# 2_10decoder1-2.net
KiCad netlist of a schematic drawn in EAGLE
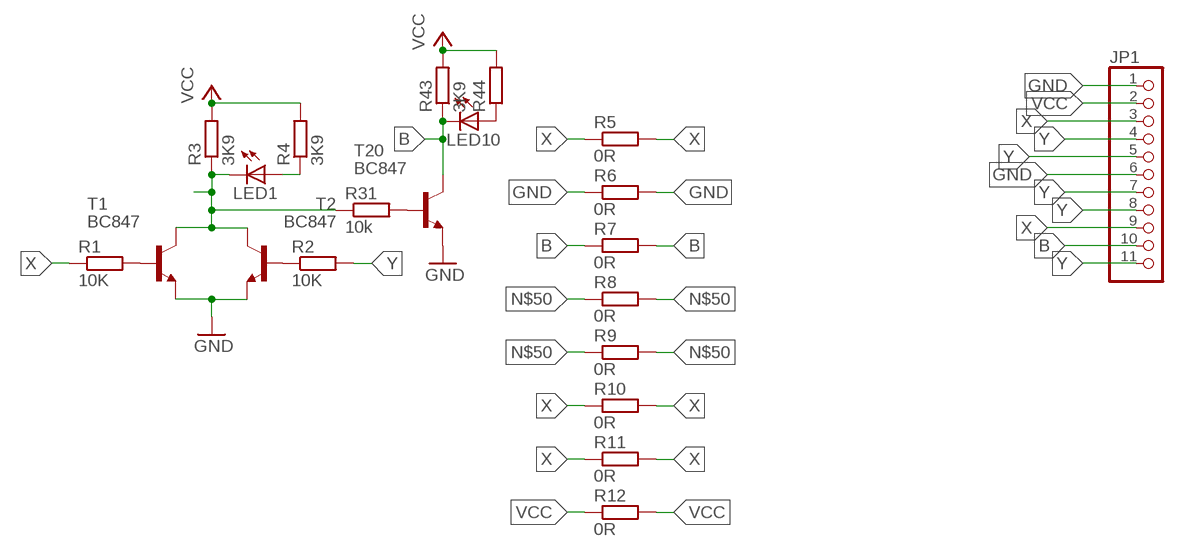
[diagram p0: schematic, sheet 1]

(export (version "E")
  (design (tool "Eeschema 10.0.6"))
  (components
    (comp (ref "JP1")
      (value "PINHD-1X11_2.54-SMD-90°")
      (footprint "eagle-import:1X11SMD_90")
      (libsource (lib "eagle-import") (part "PINHD-1X11_2.54-SMD-90°"))
    )
    (comp (ref "LED1")
      (value "LEDCHIP-LED0805")
      (footprint "eagle-import:CHIP-LED0805")
      (libsource (lib "eagle-import") (part "LEDCHIP-LED0805"))
    )
    (comp (ref "LED10")
      (value "LEDCHIP-LED0805")
      (footprint "eagle-import:CHIP-LED0805")
      (libsource (lib "eagle-import") (part "LEDCHIP-LED0805"))
    )
    (comp (ref "R1")
      (value "10K")
      (footprint "eagle-import:M0805")
      (libsource (lib "eagle-import") (part "resistor_348_R-EU_M0805"))
    )
    (comp (ref "R2")
      (value "10K")
      (footprint "eagle-import:M0805")
      (libsource (lib "eagle-import") (part "resistor_348_R-EU_M0805"))
    )
    (comp (ref "R3")
      (value "3K9")
      (footprint "eagle-import:M0805")
      (libsource (lib "eagle-import") (part "resistor_348_R-EU_M0805"))
    )
    (comp (ref "R4")
      (value "3K9")
      (footprint "eagle-import:M0805")
      (libsource (lib "eagle-import") (part "resistor_348_R-EU_M0805"))
    )
    (comp (ref "R5")
      (value "0R")
      (footprint "eagle-import:M1206")
      (libsource (lib "eagle-import") (part "R-EU_M1206"))
    )
    (comp (ref "R6")
      (value "0R")
      (footprint "eagle-import:M1206")
      (libsource (lib "eagle-import") (part "R-EU_M1206"))
    )
    (comp (ref "R7")
      (value "0R")
      (footprint "eagle-import:M1206")
      (libsource (lib "eagle-import") (part "R-EU_M1206"))
    )
    (comp (ref "R8")
      (value "0R")
      (footprint "eagle-import:M1206")
      (libsource (lib "eagle-import") (part "R-EU_M1206"))
    )
    (comp (ref "R9")
      (value "0R")
      (footprint "eagle-import:M1206")
      (libsource (lib "eagle-import") (part "R-EU_M1206"))
    )
    (comp (ref "R10")
      (value "0R")
      (footprint "eagle-import:M1206")
      (libsource (lib "eagle-import") (part "R-EU_M1206"))
    )
    (comp (ref "R11")
      (value "0R")
      (footprint "eagle-import:M1206")
      (libsource (lib "eagle-import") (part "R-EU_M1206"))
    )
    (comp (ref "R12")
      (value "0R")
      (footprint "eagle-import:M1206")
      (libsource (lib "eagle-import") (part "R-EU_M1206"))
    )
    (comp (ref "R31")
      (value "10k")
      (footprint "eagle-import:M0805")
      (libsource (lib "eagle-import") (part "resistor_348_R-EU_M0805"))
    )
    (comp (ref "R43")
      (value "3K9")
      (footprint "eagle-import:M0805")
      (libsource (lib "eagle-import") (part "resistor_348_R-EU_M0805"))
    )
    (comp (ref "R44")
      (value "R-EU_M0805")
      (footprint "eagle-import:M0805")
      (libsource (lib "eagle-import") (part "resistor_348_R-EU_M0805"))
    )
    (comp (ref "T1")
      (value "BC847")
      (footprint "eagle-import:SOT23")
      (libsource (lib "eagle-import") (part "BC847"))
    )
    (comp (ref "T2")
      (value "BC847")
      (footprint "eagle-import:SOT23")
      (libsource (lib "eagle-import") (part "BC847"))
    )
    (comp (ref "T20")
      (value "BC847")
      (footprint "eagle-import:SOT23")
      (libsource (lib "eagle-import") (part "BC847"))
    )
  )
  (nets
    (net (code "1") (name "B") (class "Default")
      (node (ref "JP1") (pin "10") (pinfunction "10_10") (pintype "passive"))
      (node (ref "LED10") (pin "C") (pinfunction "C_C") (pintype "passive"))
      (node (ref "R43") (pin "1") (pinfunction "1_1") (pintype "passive"))
      (node (ref "R7") (pin "1") (pinfunction "1_1") (pintype "passive"))
      (node (ref "R7") (pin "2") (pinfunction "2_2") (pintype "passive"))
      (node (ref "T20") (pin "3") (pinfunction "C_3") (pintype "passive"))
    )
    (net (code "2") (name "GND") (class "Default")
      (node (ref "JP1") (pin "1") (pinfunction "1_1") (pintype "passive"))
      (node (ref "JP1") (pin "6") (pinfunction "6_6") (pintype "passive"))
      (node (ref "R6") (pin "1") (pinfunction "1_1") (pintype "passive"))
      (node (ref "R6") (pin "2") (pinfunction "2_2") (pintype "passive"))
      (node (ref "T1") (pin "2") (pinfunction "E_2") (pintype "passive"))
      (node (ref "T2") (pin "2") (pinfunction "E_2") (pintype "passive"))
      (node (ref "T20") (pin "2") (pinfunction "E_2") (pintype "passive"))
    )
    (net (code "3") (name "N$50") (class "Default")
      (node (ref "LED1") (pin "C") (pinfunction "C_C") (pintype "passive"))
      (node (ref "R3") (pin "1") (pinfunction "1_1") (pintype "passive"))
      (node (ref "R31") (pin "1") (pinfunction "1_1") (pintype "passive"))
      (node (ref "R8") (pin "1") (pinfunction "1_1") (pintype "passive"))
      (node (ref "R8") (pin "2") (pinfunction "2_2") (pintype "passive"))
      (node (ref "R9") (pin "1") (pinfunction "1_1") (pintype "passive"))
      (node (ref "R9") (pin "2") (pinfunction "2_2") (pintype "passive"))
      (node (ref "T1") (pin "3") (pinfunction "C_3") (pintype "passive"))
      (node (ref "T2") (pin "3") (pinfunction "C_3") (pintype "passive"))
    )
    (net (code "4") (name "Net-(LED1-PadA)") (class "Default")
      (node (ref "LED1") (pin "A") (pinfunction "A_A") (pintype "passive"))
      (node (ref "R4") (pin "1") (pinfunction "1_1") (pintype "passive"))
    )
    (net (code "5") (name "Net-(LED10-PadA)") (class "Default")
      (node (ref "LED10") (pin "A") (pinfunction "A_A") (pintype "passive"))
      (node (ref "R44") (pin "1") (pinfunction "1_1") (pintype "passive"))
    )
    (net (code "6") (name "Net-(T1-B)") (class "Default")
      (node (ref "R1") (pin "2") (pinfunction "2_2") (pintype "passive"))
      (node (ref "T1") (pin "1") (pinfunction "B_1") (pintype "passive"))
    )
    (net (code "7") (name "Net-(T2-B)") (class "Default")
      (node (ref "R2") (pin "1") (pinfunction "1_1") (pintype "passive"))
      (node (ref "T2") (pin "1") (pinfunction "B_1") (pintype "passive"))
    )
    (net (code "8") (name "Net-(T20-B)") (class "Default")
      (node (ref "R31") (pin "2") (pinfunction "2_2") (pintype "passive"))
      (node (ref "T20") (pin "1") (pinfunction "B_1") (pintype "passive"))
    )
    (net (code "9") (name "VCC") (class "Default")
      (node (ref "JP1") (pin "2") (pinfunction "2_2") (pintype "passive"))
      (node (ref "R12") (pin "1") (pinfunction "1_1") (pintype "passive"))
      (node (ref "R12") (pin "2") (pinfunction "2_2") (pintype "passive"))
      (node (ref "R3") (pin "2") (pinfunction "2_2") (pintype "passive"))
      (node (ref "R4") (pin "2") (pinfunction "2_2") (pintype "passive"))
      (node (ref "R43") (pin "2") (pinfunction "2_2") (pintype "passive"))
      (node (ref "R44") (pin "2") (pinfunction "2_2") (pintype "passive"))
    )
    (net (code "10") (name "X") (class "Default")
      (node (ref "JP1") (pin "3") (pinfunction "3_3") (pintype "passive"))
      (node (ref "JP1") (pin "9") (pinfunction "9_9") (pintype "passive"))
      (node (ref "R1") (pin "1") (pinfunction "1_1") (pintype "passive"))
      (node (ref "R10") (pin "1") (pinfunction "1_1") (pintype "passive"))
      (node (ref "R10") (pin "2") (pinfunction "2_2") (pintype "passive"))
      (node (ref "R11") (pin "1") (pinfunction "1_1") (pintype "passive"))
      (node (ref "R11") (pin "2") (pinfunction "2_2") (pintype "passive"))
      (node (ref "R5") (pin "1") (pinfunction "1_1") (pintype "passive"))
      (node (ref "R5") (pin "2") (pinfunction "2_2") (pintype "passive"))
    )
    (net (code "11") (name "Y") (class "Default")
      (node (ref "JP1") (pin "11") (pinfunction "11_11") (pintype "passive"))
      (node (ref "JP1") (pin "4") (pinfunction "4_4") (pintype "passive"))
      (node (ref "JP1") (pin "5") (pinfunction "5_5") (pintype "passive"))
      (node (ref "JP1") (pin "7") (pinfunction "7_7") (pintype "passive"))
      (node (ref "JP1") (pin "8") (pinfunction "8_8") (pintype "passive"))
      (node (ref "R2") (pin "2") (pinfunction "2_2") (pintype "passive"))
    )
  )
)
